# CATS-EUROC-Radio_MCU.net
KiCad netlist of a schematic drawn in Altium Designer
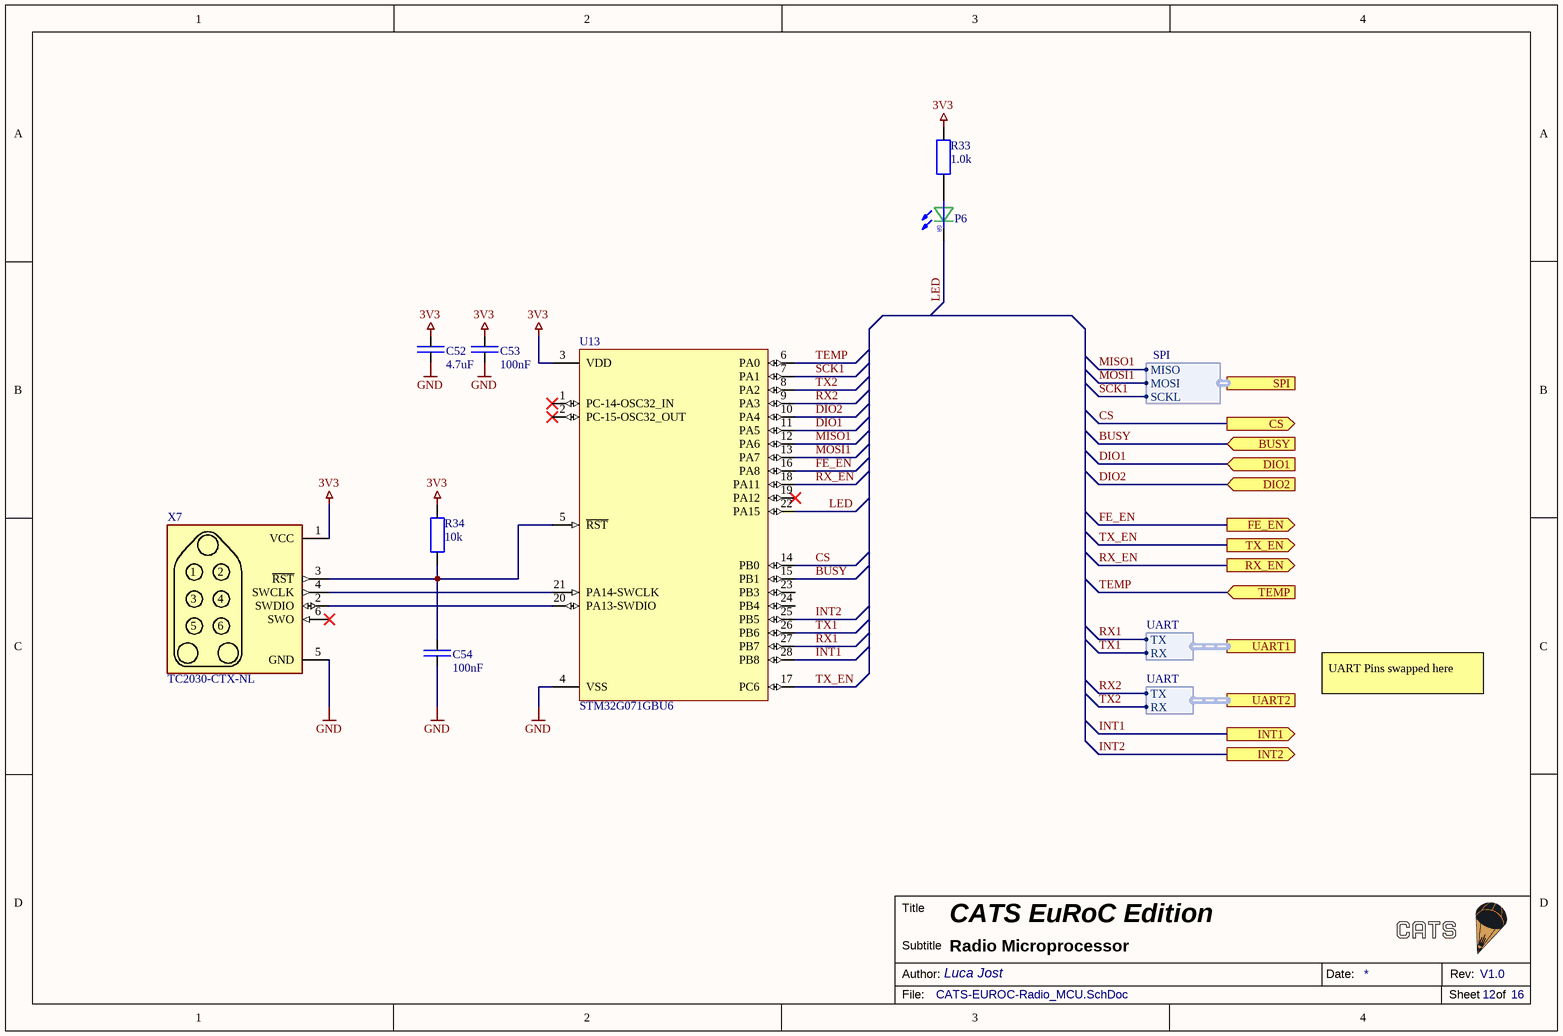
[diagram p0: CATS-EUROC-Radio_MCU.SchDoc]

(export (version "E")
  (design (tool "Eeschema 10.0.6"))
  (components
    (comp (ref "C52")
      (value "4.7uF")
      (footprint "SMD Keramikkondensator 0402")
      (description "SMD Ceramic Capacitor E6")
      (libsource (lib "CATS-EUROC") (part "E6 - 4.7uF"))
    )
    (comp (ref "C53")
      (value "100nF")
      (footprint "SMD Keramikkondensator 0402")
      (description "SMD Ceramic Capacitor E6")
      (libsource (lib "CATS-EUROC") (part "E6 - 100nF"))
    )
    (comp (ref "C54")
      (value "100nF")
      (footprint "SMD Keramikkondensator 0402")
      (description "SMD Ceramic Capacitor E6")
      (libsource (lib "CATS-EUROC") (part "E6 - 100nF"))
    )
    (comp (ref "P6")
      (value "LED")
      (footprint "SMD LED 0603")
      (description "Color LED")
      (libsource (lib "Diodes") (part "LED"))
    )
    (comp (ref "R33")
      (value "1.0k")
      (footprint "SMD Widerstand 0402")
      (description "SMD Chip Resistor E24")
      (libsource (lib "CATS-EUROC") (part "E24 - 1.0k"))
    )
    (comp (ref "R34")
      (value "10k")
      (footprint "SMD Widerstand 0402")
      (description "SMD Chip Resistor E24")
      (libsource (lib "CATS-EUROC") (part "E24 - 10k"))
    )
    (comp (ref "U13")
      (value "STM32G071GBU6")
      (footprint "SMD IC QFN-28 4x4")
      (description "ARM® Cortex®-M0+ series Microcontroller IC 32-Bit 64MHz 128KB (128K x 8) FLASH 28-UFQFPN (4x4)")
      (libsource (lib "Microcontrollers") (part "STM32G071GBU6"))
    )
    (comp (ref "X7")
      (value "TC2030-CTX-NL")
      (footprint "SMD Connector TC2030")
      (description "Tag-Connect for ARM-Cortex (6-Pin)")
      (libsource (lib "Connectors") (part "TC2030-CTX-NL"))
    )
  )
  (nets
    (net (code "3") (name "/BUSY") (class "Default")
      (node (ref "U13") (pin "15") (pinfunction "PB1_15") (pintype "bidirectional"))
    )
    (net (code "4") (name "/CS") (class "Default")
      (node (ref "U13") (pin "14") (pinfunction "PB0_14") (pintype "bidirectional"))
    )
    (net (code "5") (name "/DIO1") (class "Default")
      (node (ref "U13") (pin "11") (pinfunction "PA5_11") (pintype "bidirectional"))
    )
    (net (code "6") (name "/DIO2") (class "Default")
      (node (ref "U13") (pin "10") (pinfunction "PA4_10") (pintype "bidirectional"))
    )
    (net (code "7") (name "/FE_EN") (class "Default")
      (node (ref "U13") (pin "16") (pinfunction "PA8_16") (pintype "bidirectional"))
    )
    (net (code "8") (name "/INT1") (class "Default")
      (node (ref "U13") (pin "28") (pinfunction "PB8_28") (pintype "bidirectional"))
    )
    (net (code "9") (name "/INT2") (class "Default")
      (node (ref "U13") (pin "25") (pinfunction "PB5_25") (pintype "bidirectional"))
    )
    (net (code "10") (name "/LED") (class "Default")
      (node (ref "P6") (pin "K") (pinfunction "K_K") (pintype "passive"))
      (node (ref "U13") (pin "22") (pinfunction "PA15_22") (pintype "bidirectional"))
    )
    (net (code "11") (name "/MISO1") (class "Default")
      (node (ref "U13") (pin "12") (pinfunction "PA6_12") (pintype "bidirectional"))
    )
    (net (code "12") (name "/MOSI1") (class "Default")
      (node (ref "U13") (pin "13") (pinfunction "PA7_13") (pintype "bidirectional"))
    )
    (net (code "13") (name "/RX1") (class "Default")
      (node (ref "U13") (pin "27") (pinfunction "PB7_27") (pintype "bidirectional"))
    )
    (net (code "14") (name "/RX2") (class "Default")
      (node (ref "U13") (pin "9") (pinfunction "PA3_9") (pintype "bidirectional"))
    )
    (net (code "15") (name "/RX_EN") (class "Default")
      (node (ref "U13") (pin "18") (pinfunction "PA11_18") (pintype "bidirectional"))
    )
    (net (code "16") (name "/SCK1") (class "Default")
      (node (ref "U13") (pin "7") (pinfunction "PA1_7") (pintype "bidirectional"))
    )
    (net (code "17") (name "/TEMP") (class "Default")
      (node (ref "U13") (pin "6") (pinfunction "PA0_6") (pintype "bidirectional"))
    )
    (net (code "18") (name "/TX1") (class "Default")
      (node (ref "U13") (pin "26") (pinfunction "PB6_26") (pintype "bidirectional"))
    )
    (net (code "19") (name "/TX2") (class "Default")
      (node (ref "U13") (pin "8") (pinfunction "PA2_8") (pintype "bidirectional"))
    )
    (net (code "20") (name "/TX_EN") (class "Default")
      (node (ref "U13") (pin "17") (pinfunction "PC6_17") (pintype "bidirectional"))
    )
    (net (code "23") (name "3V3") (class "Default")
      (node (ref "C52") (pin "2") (pinfunction "2_2") (pintype "passive"))
      (node (ref "C53") (pin "2") (pinfunction "2_2") (pintype "passive"))
      (node (ref "R33") (pin "2") (pinfunction "2_2") (pintype "passive"))
      (node (ref "R34") (pin "2") (pinfunction "2_2") (pintype "passive"))
      (node (ref "U13") (pin "3") (pinfunction "VDD_3") (pintype "passive"))
      (node (ref "X7") (pin "1") (pinfunction "VCC_1") (pintype "power_in"))
    )
    (net (code "24") (name "GND") (class "Default")
      (node (ref "C52") (pin "1") (pinfunction "1_1") (pintype "passive"))
      (node (ref "C53") (pin "1") (pinfunction "1_1") (pintype "passive"))
      (node (ref "C54") (pin "1") (pinfunction "1_1") (pintype "passive"))
      (node (ref "U13") (pin "4") (pinfunction "VSS_4") (pintype "passive"))
      (node (ref "X7") (pin "5") (pinfunction "GND_5") (pintype "power_in"))
    )
    (net (code "25") (name "Net-(P6-PadA)") (class "Default")
      (node (ref "P6") (pin "A") (pinfunction "A_A") (pintype "passive"))
      (node (ref "R33") (pin "1") (pinfunction "1_1") (pintype "passive"))
    )
    (net (code "26") (name "Net-(U13-PA13-SWDIO)") (class "Default")
      (node (ref "U13") (pin "20") (pinfunction "PA13-SWDIO_20") (pintype "bidirectional"))
      (node (ref "X7") (pin "2") (pinfunction "SWDIO_2") (pintype "bidirectional"))
    )
    (net (code "27") (name "Net-(U13-PA14-SWCLK)") (class "Default")
      (node (ref "U13") (pin "21") (pinfunction "PA14-SWCLK_21") (pintype "input"))
      (node (ref "X7") (pin "4") (pinfunction "SWCLK_4") (pintype "output"))
    )
    (net (code "28") (name "Net-(U13-~{RST})") (class "Default")
      (node (ref "C54") (pin "2") (pinfunction "2_2") (pintype "passive"))
      (node (ref "R34") (pin "1") (pinfunction "1_1") (pintype "passive"))
      (node (ref "U13") (pin "5") (pinfunction "~{RST}_5") (pintype "input"))
      (node (ref "X7") (pin "3") (pinfunction "~{RST}_3") (pintype "output"))
    )
    (net (code "29") (name "unconnected-(U13-PA12-Pad19)") (class "Default")
      (node (ref "U13") (pin "19") (pinfunction "PA12_19") (pintype "bidirectional+no_connect"))
    )
    (net (code "30") (name "unconnected-(U13-PB3-Pad23)") (class "Default")
      (node (ref "U13") (pin "23") (pinfunction "PB3_23") (pintype "bidirectional"))
    )
    (net (code "31") (name "unconnected-(U13-PB4-Pad24)") (class "Default")
      (node (ref "U13") (pin "24") (pinfunction "PB4_24") (pintype "bidirectional"))
    )
    (net (code "32") (name "unconnected-(U13-PC-14-OSC32_IN-Pad1)") (class "Default")
      (node (ref "U13") (pin "1") (pinfunction "PC-14-OSC32_IN_1") (pintype "bidirectional+no_connect"))
    )
    (net (code "33") (name "unconnected-(U13-PC-15-OSC32_OUT-Pad2)") (class "Default")
      (node (ref "U13") (pin "2") (pinfunction "PC-15-OSC32_OUT_2") (pintype "bidirectional+no_connect"))
    )
    (net (code "34") (name "unconnected-(X7-SWO-Pad6)") (class "Default")
      (node (ref "X7") (pin "6") (pinfunction "SWO_6") (pintype "input+no_connect"))
    )
  )
)
